# 514_outin_arduino.net
KiCad netlist of a schematic drawn in EAGLE
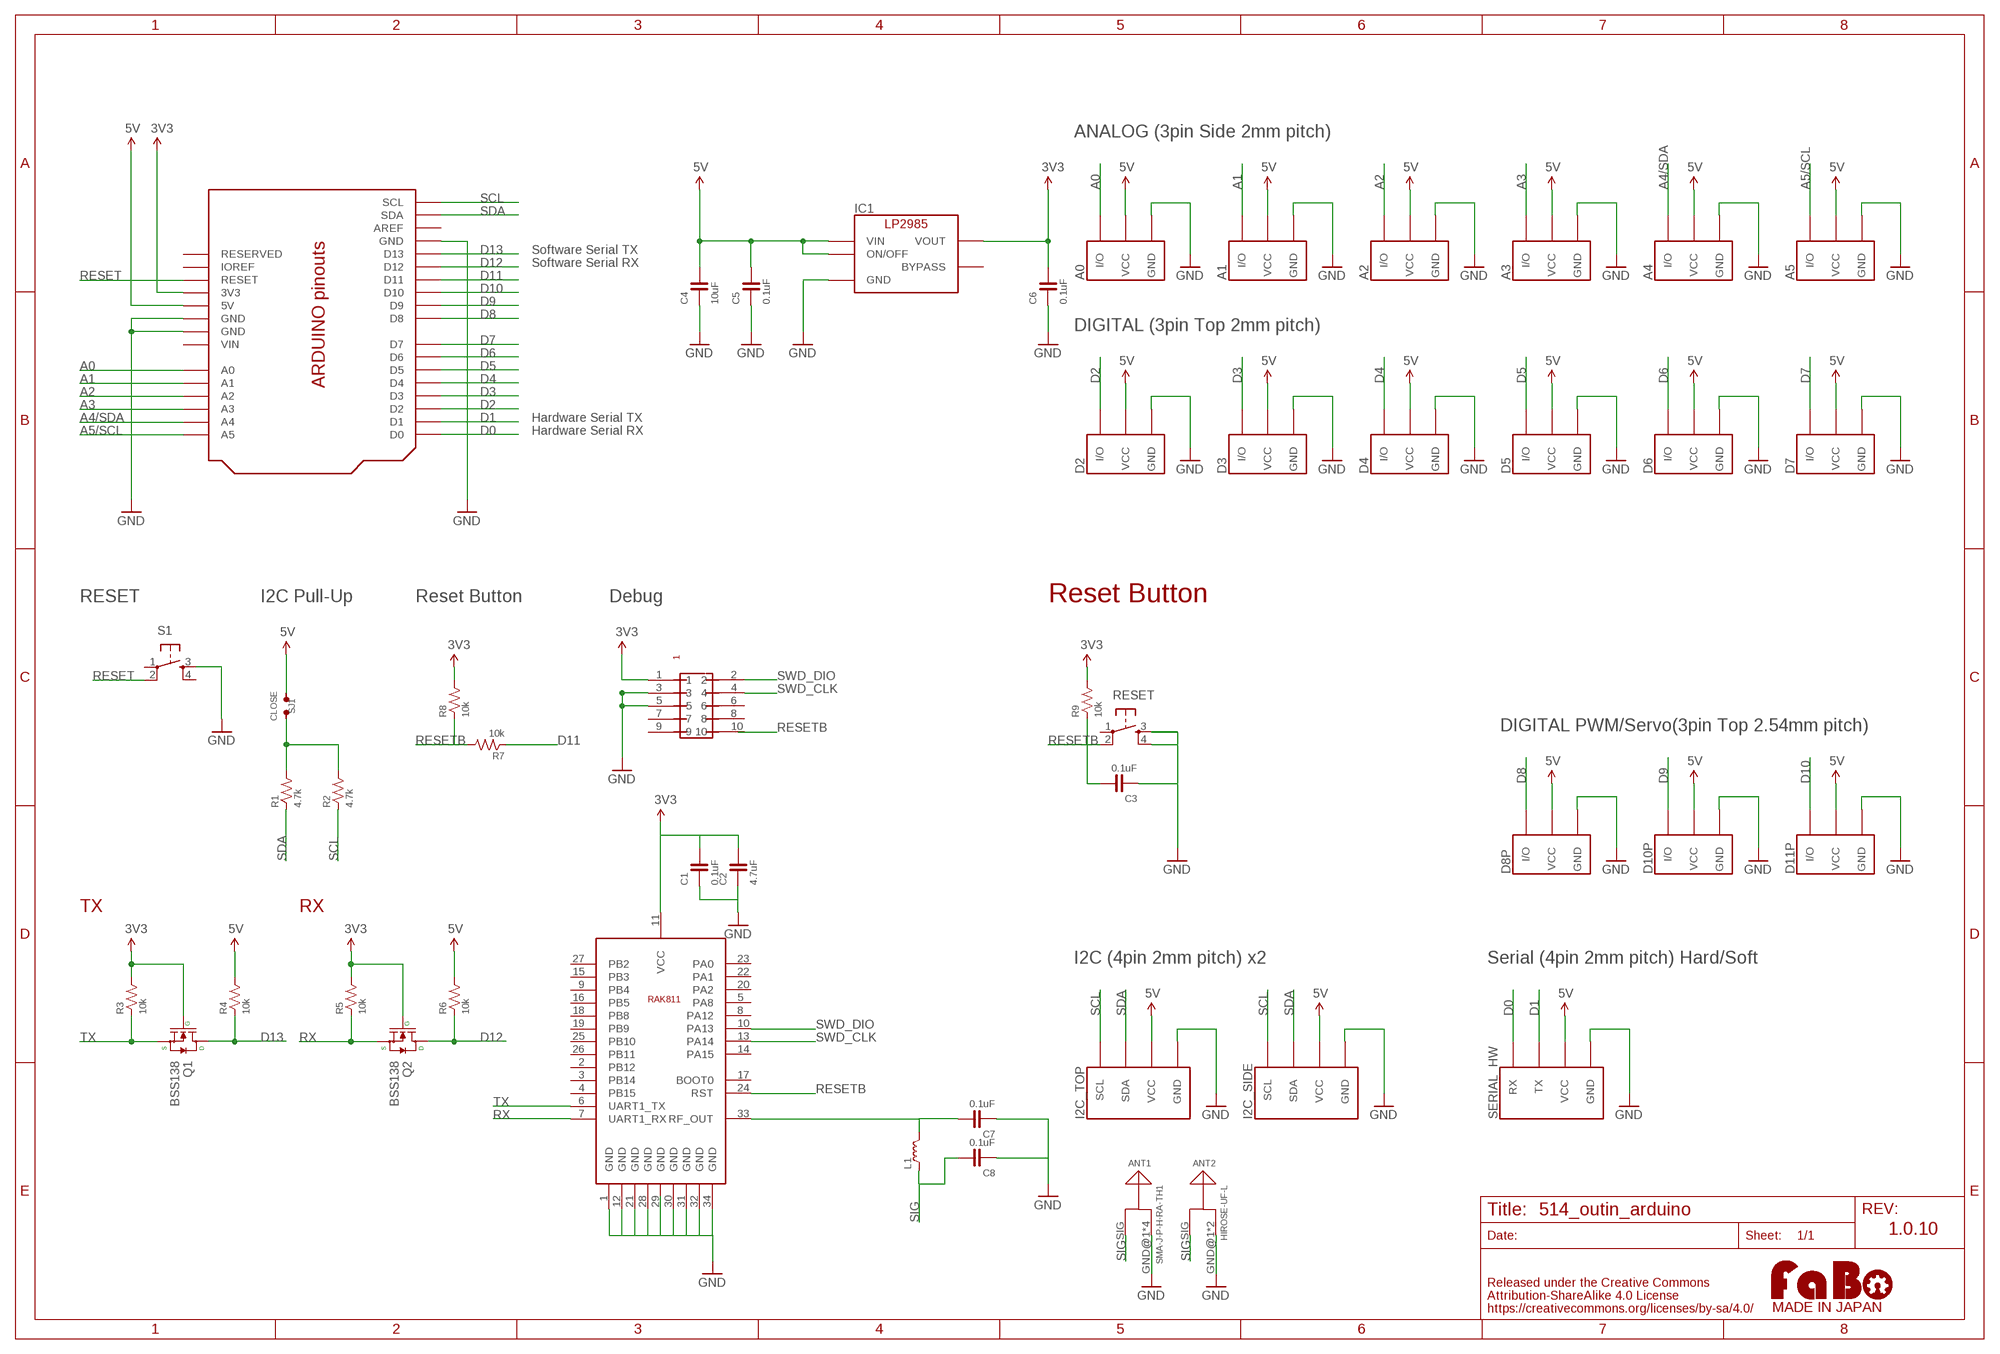
[diagram p0: schematic, sheet 1]

(export (version "E")
  (design (tool "Eeschema 10.0.6"))
  (components
    (comp (ref "A0")
      (value "FABO_BRICK_3PIN-S03B-PASK-2_LONG")
      (footprint "eagle-import:FABO_BRICK_3PIN_S03B-PASK-2_LONG")
      (libsource (lib "eagle-import") (part "FABO_BRICK_3PIN-S03B-PASK-2_LONG"))
    )
    (comp (ref "A1")
      (value "FABO_BRICK_3PIN-S03B-PASK-2_LONG")
      (footprint "eagle-import:FABO_BRICK_3PIN_S03B-PASK-2_LONG")
      (libsource (lib "eagle-import") (part "FABO_BRICK_3PIN-S03B-PASK-2_LONG"))
    )
    (comp (ref "A2")
      (value "FABO_BRICK_3PIN-S03B-PASK-2_LONG")
      (footprint "eagle-import:FABO_BRICK_3PIN_S03B-PASK-2_LONG")
      (libsource (lib "eagle-import") (part "FABO_BRICK_3PIN-S03B-PASK-2_LONG"))
    )
    (comp (ref "A3")
      (value "FABO_BRICK_3PIN-S03B-PASK-2_LONG")
      (footprint "eagle-import:FABO_BRICK_3PIN_S03B-PASK-2_LONG")
      (libsource (lib "eagle-import") (part "FABO_BRICK_3PIN-S03B-PASK-2_LONG"))
    )
    (comp (ref "A4")
      (value "FABO_BRICK_3PIN-S03B-PASK-2_LONG")
      (footprint "eagle-import:FABO_BRICK_3PIN_S03B-PASK-2_LONG")
      (libsource (lib "eagle-import") (part "FABO_BRICK_3PIN-S03B-PASK-2_LONG"))
    )
    (comp (ref "A5")
      (value "FABO_BRICK_3PIN-S03B-PASK-2_LONG")
      (footprint "eagle-import:FABO_BRICK_3PIN_S03B-PASK-2_LONG")
      (libsource (lib "eagle-import") (part "FABO_BRICK_3PIN-S03B-PASK-2_LONG"))
    )
    (comp (ref "ANT1")
      (value "SMA-J-P-H-RA-TH1")
      (footprint "eagle-import:SMA–J–P–H–RA–TH1")
      (libsource (lib "eagle-import") (part "ANTENA_SMA-J-P-H-RA-TH1"))
    )
    (comp (ref "ANT2")
      (value "HIROSE-UF-L")
      (footprint "eagle-import:HIROSE-UF-L")
      (libsource (lib "eagle-import") (part "ANTENA_HIROSE-UF-L"))
    )
    (comp (ref "C1")
      (value "0.1uF")
      (footprint "eagle-import:0603-NARROW")
      (libsource (lib "eagle-import") (part "CAPACITOR-0603_NARROW"))
    )
    (comp (ref "C2")
      (value "4.7uF")
      (footprint "eagle-import:0603-NARROW")
      (libsource (lib "eagle-import") (part "CAPACITOR-0603_NARROW"))
    )
    (comp (ref "C3")
      (value "0.1uF")
      (footprint "eagle-import:0603-NARROW")
      (libsource (lib "eagle-import") (part "CAPACITOR-0603_NARROW"))
    )
    (comp (ref "C4")
      (value "10uF")
      (footprint "eagle-import:0603-NARROW")
      (libsource (lib "eagle-import") (part "CAPACITOR-0603_NARROW"))
    )
    (comp (ref "C5")
      (value "0.1uF")
      (footprint "eagle-import:0603-NARROW")
      (libsource (lib "eagle-import") (part "CAPACITOR-0603_NARROW"))
    )
    (comp (ref "C6")
      (value "0.1uF")
      (footprint "eagle-import:0603-NARROW")
      (libsource (lib "eagle-import") (part "CAPACITOR-0603_NARROW"))
    )
    (comp (ref "C7")
      (value "0.1uF")
      (footprint "eagle-import:0603-NARROW")
      (libsource (lib "eagle-import") (part "CAPACITOR-0603_NARROW"))
    )
    (comp (ref "C8")
      (value "0.1uF")
      (footprint "eagle-import:0603-NARROW")
      (libsource (lib "eagle-import") (part "CAPACITOR-0603_NARROW"))
    )
    (comp (ref "D2")
      (value "FABO_BRICK_3PIN-B03B-PASK-1")
      (footprint "eagle-import:FABO_BRICK_3PIN_B03B-PASK-1")
      (libsource (lib "eagle-import") (part "FABO_BRICK_3PIN-B03B-PASK-1"))
    )
    (comp (ref "D3")
      (value "FABO_BRICK_3PIN-B03B-PASK-1")
      (footprint "eagle-import:FABO_BRICK_3PIN_B03B-PASK-1")
      (libsource (lib "eagle-import") (part "FABO_BRICK_3PIN-B03B-PASK-1"))
    )
    (comp (ref "D4")
      (value "FABO_BRICK_3PIN-B03B-PASK-1")
      (footprint "eagle-import:FABO_BRICK_3PIN_B03B-PASK-1")
      (libsource (lib "eagle-import") (part "FABO_BRICK_3PIN-B03B-PASK-1"))
    )
    (comp (ref "D5")
      (value "FABO_BRICK_3PIN-B03B-PASK-1")
      (footprint "eagle-import:FABO_BRICK_3PIN_B03B-PASK-1")
      (libsource (lib "eagle-import") (part "FABO_BRICK_3PIN-B03B-PASK-1"))
    )
    (comp (ref "D6")
      (value "FABO_BRICK_3PIN-B03B-PASK-1")
      (footprint "eagle-import:FABO_BRICK_3PIN_B03B-PASK-1")
      (libsource (lib "eagle-import") (part "FABO_BRICK_3PIN-B03B-PASK-1"))
    )
    (comp (ref "D7")
      (value "FABO_BRICK_3PIN-B03B-PASK-1")
      (footprint "eagle-import:FABO_BRICK_3PIN_B03B-PASK-1")
      (libsource (lib "eagle-import") (part "FABO_BRICK_3PIN-B03B-PASK-1"))
    )
    (comp (ref "D8P")
      (value "FABO_BRICK_3PIN-HEADER")
      (footprint "eagle-import:FABO_BRICK_3PIN_HEADER")
      (libsource (lib "eagle-import") (part "FABO_BRICK_3PIN-HEADER"))
    )
    (comp (ref "D10P")
      (value "FABO_BRICK_3PIN-HEADER")
      (footprint "eagle-import:FABO_BRICK_3PIN_HEADER")
      (libsource (lib "eagle-import") (part "FABO_BRICK_3PIN-HEADER"))
    )
    (comp (ref "D11P")
      (value "FABO_BRICK_3PIN-HEADER")
      (footprint "eagle-import:FABO_BRICK_3PIN_HEADER")
      (libsource (lib "eagle-import") (part "FABO_BRICK_3PIN-HEADER"))
    )
    (comp (ref "I2C_SIDE")
      (value "FABO_BRICK_I2C-S04B-PASK-2_LONG")
      (footprint "eagle-import:FABO_BRICK_I2C_S04B-PASK-2_LONG")
      (libsource (lib "eagle-import") (part "FABO_BRICK_I2C-S04B-PASK-2_LONG"))
    )
    (comp (ref "I2C_TOP")
      (value "FABO_BRICK_I2C-B04B-PASK-1")
      (footprint "eagle-import:FABO_BRICK_I2C_B04B-PASK-1")
      (libsource (lib "eagle-import") (part "FABO_BRICK_I2C-B04B-PASK-1"))
    )
    (comp (ref "IC1")
      (value "LP2985-33DBV")
      (footprint "eagle-import:SOT-23-5")
      (libsource (lib "eagle-import") (part "LP2985-33DBV"))
    )
    (comp (ref "L1")
      (value "COIL-0603")
      (footprint "eagle-import:0603")
      (libsource (lib "eagle-import") (part "COIL-0603"))
    )
    (comp (ref "Q1")
      (value "BSS138")
      (footprint "eagle-import:SOT23-3")
      (libsource (lib "eagle-import") (part "MOSFET-N"))
    )
    (comp (ref "Q2")
      (value "BSS138")
      (footprint "eagle-import:SOT23-3")
      (libsource (lib "eagle-import") (part "MOSFET-N"))
    )
    (comp (ref "R1")
      (value "4.7k")
      (footprint "eagle-import:0603")
      (libsource (lib "eagle-import") (part "RESISTOR-0603"))
    )
    (comp (ref "R2")
      (value "4.7k")
      (footprint "eagle-import:0603")
      (libsource (lib "eagle-import") (part "RESISTOR-0603"))
    )
    (comp (ref "R3")
      (value "10k")
      (footprint "eagle-import:0603-NARROW")
      (libsource (lib "eagle-import") (part "RESISTOR-0603-NARROW"))
    )
    (comp (ref "R4")
      (value "10k")
      (footprint "eagle-import:0603-NARROW")
      (libsource (lib "eagle-import") (part "RESISTOR-0603-NARROW"))
    )
    (comp (ref "R5")
      (value "10k")
      (footprint "eagle-import:0603-NARROW")
      (libsource (lib "eagle-import") (part "RESISTOR-0603-NARROW"))
    )
    (comp (ref "R6")
      (value "10k")
      (footprint "eagle-import:0603-NARROW")
      (libsource (lib "eagle-import") (part "RESISTOR-0603-NARROW"))
    )
    (comp (ref "R7")
      (value "10k")
      (footprint "eagle-import:0603-NARROW")
      (libsource (lib "eagle-import") (part "RESISTOR-0603-NARROW"))
    )
    (comp (ref "R8")
      (value "10k")
      (footprint "eagle-import:0603-NARROW")
      (libsource (lib "eagle-import") (part "RESISTOR-0603-NARROW"))
    )
    (comp (ref "R9")
      (value "10k")
      (footprint "eagle-import:0603-NARROW")
      (libsource (lib "eagle-import") (part "RESISTOR-0603-NARROW"))
    )
    (comp (ref "RESET")
      (value "TACT-SWITCH-SMD_KMR2")
      (footprint "eagle-import:KMR2")
      (libsource (lib "eagle-import") (part "TACT-SWITCH-SMD_KMR2"))
    )
    (comp (ref "S1")
      (value "TACT-SWITCH-6MM")
      (footprint "eagle-import:DTS_6_V")
      (libsource (lib "eagle-import") (part "TACT-SWITCH-6MM"))
    )
    (comp (ref "SERIAL_HW")
      (value "FABO_BRICK_SERIAL-B04B-PASK-1")
      (footprint "eagle-import:FABO_BRICK_SERIAL_B04B-PASK-1")
      (libsource (lib "eagle-import") (part "FABO_BRICK_SERIAL-B04B-PASK-1"))
    )
    (comp (ref "SJ1")
      (value "CLOSE")
      (footprint "eagle-import:SMD-JUMPER-0603")
      (libsource (lib "eagle-import") (part "SMD-JUMPER-2-0603"))
    )
    (comp (ref "U$3")
      (value "RAK811")
      (footprint "eagle-import:RAK811")
      (libsource (lib "eagle-import") (part "RAK811"))
    )
    (comp (ref "U$10")
      (value "LOGO_FABO-M")
      (footprint "eagle-import:LOGO_FABO_MS")
      (libsource (lib "eagle-import") (part "LOGO_FABO-M"))
    )
    (comp (ref "U$15")
      (value "PIN-HEADER-SMT(1.27MM)2X5")
      (footprint "eagle-import:PIN-HEADER-SMT(1.27MM)2X5")
      (libsource (lib "eagle-import") (part "PIN-HEADER-SMT(1.27MM)2X5"))
    )
    (comp (ref "U1")
      (value "ARDUINO_UNO_R3_SHIELD-OUTIN")
      (footprint "eagle-import:ARDUINO_SHIELD_OUTIN")
      (libsource (lib "eagle-import") (part "ARDUINO_UNO_R3_SHIELD-OUTIN"))
    )
  )
  (nets
    (net (code "1") (name "/A0") (class "Default")
      (node (ref "A0") (pin "I/O") (pinfunction "I/O_I/O") (pintype "bidirectional"))
      (node (ref "U1") (pin "A0") (pinfunction "A0_A0") (pintype "bidirectional"))
    )
    (net (code "2") (name "/A1") (class "Default")
      (node (ref "A1") (pin "I/O") (pinfunction "I/O_I/O") (pintype "bidirectional"))
      (node (ref "U1") (pin "A1") (pinfunction "A1_A1") (pintype "bidirectional"))
    )
    (net (code "3") (name "/A2") (class "Default")
      (node (ref "A2") (pin "I/O") (pinfunction "I/O_I/O") (pintype "bidirectional"))
      (node (ref "U1") (pin "A2") (pinfunction "A2_A2") (pintype "bidirectional"))
    )
    (net (code "4") (name "/A3") (class "Default")
      (node (ref "A3") (pin "I/O") (pinfunction "I/O_I/O") (pintype "bidirectional"))
      (node (ref "U1") (pin "A3") (pinfunction "A3_A3") (pintype "bidirectional"))
    )
    (net (code "5") (name "/A4{slash}SDA") (class "Default")
      (node (ref "A4") (pin "I/O") (pinfunction "I/O_I/O") (pintype "bidirectional"))
      (node (ref "U1") (pin "A4") (pinfunction "A4_A4") (pintype "bidirectional"))
    )
    (net (code "6") (name "/A5{slash}SCL") (class "Default")
      (node (ref "A5") (pin "I/O") (pinfunction "I/O_I/O") (pintype "bidirectional"))
      (node (ref "U1") (pin "A5") (pinfunction "A5_A5") (pintype "bidirectional"))
    )
    (net (code "7") (name "/D0") (class "Default")
      (node (ref "SERIAL_HW") (pin "RX") (pinfunction "RX_RX") (pintype "bidirectional"))
      (node (ref "U1") (pin "D0") (pinfunction "D0_D0") (pintype "bidirectional"))
    )
    (net (code "8") (name "/D1") (class "Default")
      (node (ref "SERIAL_HW") (pin "TX") (pinfunction "TX_TX") (pintype "bidirectional"))
      (node (ref "U1") (pin "D1") (pinfunction "D1_D1") (pintype "bidirectional"))
    )
    (net (code "9") (name "/D2") (class "Default")
      (node (ref "D2") (pin "I/O") (pinfunction "I/O_I/O") (pintype "bidirectional"))
      (node (ref "U1") (pin "D2") (pinfunction "D2_D2") (pintype "bidirectional"))
    )
    (net (code "10") (name "/D3") (class "Default")
      (node (ref "D3") (pin "I/O") (pinfunction "I/O_I/O") (pintype "bidirectional"))
      (node (ref "U1") (pin "D3") (pinfunction "D3_D3") (pintype "bidirectional"))
    )
    (net (code "11") (name "/D4") (class "Default")
      (node (ref "D4") (pin "I/O") (pinfunction "I/O_I/O") (pintype "bidirectional"))
      (node (ref "U1") (pin "D4") (pinfunction "D4_D4") (pintype "bidirectional"))
    )
    (net (code "12") (name "/D5") (class "Default")
      (node (ref "D5") (pin "I/O") (pinfunction "I/O_I/O") (pintype "bidirectional"))
      (node (ref "U1") (pin "D5") (pinfunction "D5_D5") (pintype "bidirectional"))
    )
    (net (code "13") (name "/D6") (class "Default")
      (node (ref "D6") (pin "I/O") (pinfunction "I/O_I/O") (pintype "bidirectional"))
      (node (ref "U1") (pin "D6") (pinfunction "D6_D6") (pintype "bidirectional"))
    )
    (net (code "14") (name "/D7") (class "Default")
      (node (ref "D7") (pin "I/O") (pinfunction "I/O_I/O") (pintype "bidirectional"))
      (node (ref "U1") (pin "D7") (pinfunction "D7_D7") (pintype "bidirectional"))
    )
    (net (code "15") (name "/D8") (class "Default")
      (node (ref "D8P") (pin "I/O") (pinfunction "I/O_I/O") (pintype "bidirectional"))
      (node (ref "U1") (pin "D8") (pinfunction "D8_D8") (pintype "bidirectional"))
    )
    (net (code "16") (name "/D9") (class "Default")
      (node (ref "D10P") (pin "I/O") (pinfunction "I/O_I/O") (pintype "bidirectional"))
      (node (ref "U1") (pin "D9") (pinfunction "D9_D9") (pintype "bidirectional"))
    )
    (net (code "17") (name "/D10") (class "Default")
      (node (ref "D11P") (pin "I/O") (pinfunction "I/O_I/O") (pintype "bidirectional"))
      (node (ref "U1") (pin "D10") (pinfunction "D10_D10") (pintype "bidirectional"))
    )
    (net (code "18") (name "/D11") (class "Default")
      (node (ref "R7") (pin "1") (pinfunction "1_1") (pintype "bidirectional"))
      (node (ref "U1") (pin "D11") (pinfunction "D11_D11") (pintype "bidirectional"))
    )
    (net (code "19") (name "/D12") (class "Default")
      (node (ref "Q2") (pin "3") (pinfunction "D_3") (pintype "passive"))
      (node (ref "R6") (pin "1") (pinfunction "1_1") (pintype "bidirectional"))
      (node (ref "U1") (pin "D12") (pinfunction "D12_D12") (pintype "bidirectional"))
    )
    (net (code "20") (name "/D13") (class "Default")
      (node (ref "Q1") (pin "3") (pinfunction "D_3") (pintype "passive"))
      (node (ref "R4") (pin "1") (pinfunction "1_1") (pintype "bidirectional"))
      (node (ref "U1") (pin "D13") (pinfunction "D13_D13") (pintype "bidirectional"))
    )
    (net (code "21") (name "/RESET") (class "Default")
      (node (ref "S1") (pin "2") (pinfunction "2_2") (pintype "passive"))
      (node (ref "U1") (pin "RESET") (pinfunction "RESET_RESET") (pintype "bidirectional"))
    )
    (net (code "22") (name "/RESETB") (class "Default")
      (node (ref "C3") (pin "2") (pinfunction "2_2") (pintype "passive"))
      (node (ref "R7") (pin "2") (pinfunction "2_2") (pintype "bidirectional"))
      (node (ref "R8") (pin "1") (pinfunction "1_1") (pintype "bidirectional"))
      (node (ref "R9") (pin "1") (pinfunction "1_1") (pintype "bidirectional"))
      (node (ref "RESET") (pin "2") (pinfunction "2_2") (pintype "passive"))
      (node (ref "U$15") (pin "10") (pinfunction "10_10") (pintype "bidirectional"))
      (node (ref "U$3") (pin "24") (pinfunction "RST_24") (pintype "bidirectional"))
    )
    (net (code "23") (name "/RX") (class "Default")
      (node (ref "Q2") (pin "2") (pinfunction "S_2") (pintype "passive"))
      (node (ref "R5") (pin "1") (pinfunction "1_1") (pintype "bidirectional"))
      (node (ref "U$3") (pin "7") (pinfunction "UART1_RX_7") (pintype "bidirectional"))
    )
    (net (code "24") (name "/SCL") (class "Default")
      (node (ref "I2C_SIDE") (pin "SCL") (pinfunction "SCL_SCL") (pintype "bidirectional"))
      (node (ref "I2C_TOP") (pin "SCL") (pinfunction "SCL_SCL") (pintype "bidirectional"))
      (node (ref "R2") (pin "1") (pinfunction "1_1") (pintype "bidirectional"))
      (node (ref "U1") (pin "SCL") (pinfunction "SCL_SCL") (pintype "bidirectional"))
    )
    (net (code "25") (name "/SDA") (class "Default")
      (node (ref "I2C_SIDE") (pin "SDA") (pinfunction "SDA_SDA") (pintype "bidirectional"))
      (node (ref "I2C_TOP") (pin "SDA") (pinfunction "SDA_SDA") (pintype "bidirectional"))
      (node (ref "R1") (pin "1") (pinfunction "1_1") (pintype "bidirectional"))
      (node (ref "U1") (pin "SDA") (pinfunction "SDA_SDA") (pintype "bidirectional"))
    )
    (net (code "26") (name "/SIG") (class "Default")
      (node (ref "ANT1") (pin "SIG") (pinfunction "SIG_SIG") (pintype "passive"))
      (node (ref "ANT2") (pin "SIG") (pinfunction "SIG_SIG") (pintype "passive"))
      (node (ref "C8") (pin "2") (pinfunction "2_2") (pintype "passive"))
      (node (ref "L1") (pin "1") (pinfunction "1_1") (pintype "bidirectional"))
    )
    (net (code "27") (name "/SWD_CLK") (class "Default")
      (node (ref "U$15") (pin "4") (pinfunction "4_4") (pintype "bidirectional"))
      (node (ref "U$3") (pin "13") (pinfunction "PA14_13") (pintype "bidirectional"))
    )
    (net (code "28") (name "/SWD_DIO") (class "Default")
      (node (ref "U$15") (pin "2") (pinfunction "2_2") (pintype "bidirectional"))
      (node (ref "U$3") (pin "10") (pinfunction "PA13_10") (pintype "bidirectional"))
    )
    (net (code "29") (name "/TX") (class "Default")
      (node (ref "Q1") (pin "2") (pinfunction "S_2") (pintype "passive"))
      (node (ref "R3") (pin "1") (pinfunction "1_1") (pintype "bidirectional"))
      (node (ref "U$3") (pin "6") (pinfunction "UART1_TX_6") (pintype "bidirectional"))
    )
    (net (code "30") (name "/VIN") (class "Default")
      (node (ref "U1") (pin "VIN") (pinfunction "VIN_VIN") (pintype "power_in"))
    )
    (net (code "31") (name "3V3") (class "Default")
      (node (ref "C1") (pin "2") (pinfunction "2_2") (pintype "passive"))
      (node (ref "C2") (pin "2") (pinfunction "2_2") (pintype "passive"))
      (node (ref "C6") (pin "2") (pinfunction "2_2") (pintype "passive"))
      (node (ref "IC1") (pin "5") (pinfunction "VOUT_5") (pintype "output"))
      (node (ref "Q1") (pin "1") (pinfunction "G_1") (pintype "passive"))
      (node (ref "Q2") (pin "1") (pinfunction "G_1") (pintype "passive"))
      (node (ref "R3") (pin "2") (pinfunction "2_2") (pintype "bidirectional"))
      (node (ref "R5") (pin "2") (pinfunction "2_2") (pintype "bidirectional"))
      (node (ref "R8") (pin "2") (pinfunction "2_2") (pintype "bidirectional"))
      (node (ref "R9") (pin "2") (pinfunction "2_2") (pintype "bidirectional"))
      (node (ref "U$15") (pin "1") (pinfunction "1_1") (pintype "bidirectional"))
      (node (ref "U$3") (pin "11") (pinfunction "VCC_11") (pintype "bidirectional"))
      (node (ref "U1") (pin "3V3") (pinfunction "3V3_3V3") (pintype "power_in"))
    )
    (net (code "32") (name "5V") (class "Default")
      (node (ref "A0") (pin "VCC") (pinfunction "VCC_VCC") (pintype "bidirectional"))
      (node (ref "A1") (pin "VCC") (pinfunction "VCC_VCC") (pintype "bidirectional"))
      (node (ref "A2") (pin "VCC") (pinfunction "VCC_VCC") (pintype "bidirectional"))
      (node (ref "A3") (pin "VCC") (pinfunction "VCC_VCC") (pintype "bidirectional"))
      (node (ref "A4") (pin "VCC") (pinfunction "VCC_VCC") (pintype "bidirectional"))
      (node (ref "A5") (pin "VCC") (pinfunction "VCC_VCC") (pintype "bidirectional"))
      (node (ref "C4") (pin "2") (pinfunction "2_2") (pintype "passive"))
      (node (ref "C5") (pin "2") (pinfunction "2_2") (pintype "passive"))
      (node (ref "D10P") (pin "VCC") (pinfunction "VCC_VCC") (pintype "bidirectional"))
      (node (ref "D11P") (pin "VCC") (pinfunction "VCC_VCC") (pintype "bidirectional"))
      (node (ref "D2") (pin "VCC") (pinfunction "VCC_VCC") (pintype "bidirectional"))
      (node (ref "D3") (pin "VCC") (pinfunction "VCC_VCC") (pintype "bidirectional"))
      (node (ref "D4") (pin "VCC") (pinfunction "VCC_VCC") (pintype "bidirectional"))
      (node (ref "D5") (pin "VCC") (pinfunction "VCC_VCC") (pintype "bidirectional"))
      (node (ref "D6") (pin "VCC") (pinfunction "VCC_VCC") (pintype "bidirectional"))
      (node (ref "D7") (pin "VCC") (pinfunction "VCC_VCC") (pintype "bidirectional"))
      (node (ref "D8P") (pin "VCC") (pinfunction "VCC_VCC") (pintype "bidirectional"))
      (node (ref "I2C_SIDE") (pin "VCC") (pinfunction "VCC_VCC") (pintype "bidirectional"))
      (node (ref "I2C_TOP") (pin "VCC") (pinfunction "VCC_VCC") (pintype "bidirectional"))
      (node (ref "IC1") (pin "1") (pinfunction "VIN_1") (pintype "input"))
      (node (ref "IC1") (pin "3") (pinfunction "ON/OFF_3") (pintype "input"))
      (node (ref "R4") (pin "2") (pinfunction "2_2") (pintype "bidirectional"))
      (node (ref "R6") (pin "2") (pinfunction "2_2") (pintype "bidirectional"))
      (node (ref "SERIAL_HW") (pin "VCC") (pinfunction "VCC_VCC") (pintype "bidirectional"))
      (node (ref "SJ1") (pin "1") (pinfunction "1_1") (pintype "passive"))
      (node (ref "U1") (pin "5V") (pinfunction "5V_5V") (pintype "power_in"))
    )
    (net (code "33") (name "GND") (class "Default")
      (node (ref "A0") (pin "GND") (pinfunction "GND_GND") (pintype "bidirectional"))
      (node (ref "A1") (pin "GND") (pinfunction "GND_GND") (pintype "bidirectional"))
      (node (ref "A2") (pin "GND") (pinfunction "GND_GND") (pintype "bidirectional"))
      (node (ref "A3") (pin "GND") (pinfunction "GND_GND") (pintype "bidirectional"))
      (node (ref "A4") (pin "GND") (pinfunction "GND_GND") (pintype "bidirectional"))
      (node (ref "A5") (pin "GND") (pinfunction "GND_GND") (pintype "bidirectional"))
      (node (ref "ANT1") (pin "GND@1") (pinfunction "GND_GND@1") (pintype "passive"))
      (node (ref "ANT1") (pin "GND@2") (pinfunction "GND_GND@2") (pintype "passive"))
      (node (ref "ANT1") (pin "GND@3") (pinfunction "GND_GND@3") (pintype "passive"))
      (node (ref "ANT1") (pin "GND@4") (pinfunction "GND_GND@4") (pintype "passive"))
      (node (ref "ANT2") (pin "GND@1") (pinfunction "GND_GND@1") (pintype "passive"))
      (node (ref "ANT2") (pin "GND@2") (pinfunction "GND_GND@2") (pintype "passive"))
      (node (ref "C1") (pin "1") (pinfunction "1_1") (pintype "passive"))
      (node (ref "C2") (pin "1") (pinfunction "1_1") (pintype "passive"))
      (node (ref "C3") (pin "1") (pinfunction "1_1") (pintype "passive"))
      (node (ref "C4") (pin "1") (pinfunction "1_1") (pintype "passive"))
      (node (ref "C5") (pin "1") (pinfunction "1_1") (pintype "passive"))
      (node (ref "C6") (pin "1") (pinfunction "1_1") (pintype "passive"))
      (node (ref "C7") (pin "1") (pinfunction "1_1") (pintype "passive"))
      (node (ref "C8") (pin "1") (pinfunction "1_1") (pintype "passive"))
      (node (ref "D10P") (pin "GND") (pinfunction "GND_GND") (pintype "bidirectional"))
      (node (ref "D11P") (pin "GND") (pinfunction "GND_GND") (pintype "bidirectional"))
      (node (ref "D2") (pin "GND") (pinfunction "GND_GND") (pintype "bidirectional"))
      (node (ref "D3") (pin "GND") (pinfunction "GND_GND") (pintype "bidirectional"))
      (node (ref "D4") (pin "GND") (pinfunction "GND_GND") (pintype "bidirectional"))
      (node (ref "D5") (pin "GND") (pinfunction "GND_GND") (pintype "bidirectional"))
      (node (ref "D6") (pin "GND") (pinfunction "GND_GND") (pintype "bidirectional"))
      (node (ref "D7") (pin "GND") (pinfunction "GND_GND") (pintype "bidirectional"))
      (node (ref "D8P") (pin "GND") (pinfunction "GND_GND") (pintype "bidirectional"))
      (node (ref "I2C_SIDE") (pin "GND") (pinfunction "GND_GND") (pintype "bidirectional"))
      (node (ref "I2C_TOP") (pin "GND") (pinfunction "GND_GND") (pintype "bidirectional"))
      (node (ref "IC1") (pin "2") (pinfunction "GND_2") (pintype "power_in"))
      (node (ref "RESET") (pin "3") (pinfunction "3_3") (pintype "passive"))
      (node (ref "RESET") (pin "4") (pinfunction "4_4") (pintype "passive"))
      (node (ref "S1") (pin "3") (pinfunction "3_3") (pintype "passive"))
      (node (ref "SERIAL_HW") (pin "GND") (pinfunction "GND_GND") (pintype "bidirectional"))
      (node (ref "U$15") (pin "3") (pinfunction "3_3") (pintype "bidirectional"))
      (node (ref "U$15") (pin "5") (pinfunction "5_5") (pintype "bidirectional"))
      (node (ref "U$3") (pin "1") (pinfunction "GND_1") (pintype "bidirectional"))
      (node (ref "U$3") (pin "12") (pinfunction "GND_12") (pintype "bidirectional"))
      (node (ref "U$3") (pin "21") (pinfunction "GND_21") (pintype "bidirectional"))
      (node (ref "U$3") (pin "28") (pinfunction "GND_28") (pintype "bidirectional"))
      (node (ref "U$3") (pin "30") (pinfunction "GND_30") (pintype "bidirectional"))
      (node (ref "U$3") (pin "31") (pinfunction "GND_31") (pintype "bidirectional"))
      (node (ref "U$3") (pin "32") (pinfunction "GND_32") (pintype "bidirectional"))
      (node (ref "U$3") (pin "34") (pinfunction "GND_34") (pintype "bidirectional"))
      (node (ref "U1") (pin "GND1") (pinfunction "GND_GND1") (pintype "power_in"))
      (node (ref "U1") (pin "GND2") (pinfunction "GND_GND2") (pintype "power_in"))
      (node (ref "U1") (pin "GND3") (pinfunction "GND_GND3") (pintype "power_in"))
    )
    (net (code "34") (name "Net-(R1-Pad2)") (class "Default")
      (node (ref "R1") (pin "2") (pinfunction "2_2") (pintype "bidirectional"))
      (node (ref "R2") (pin "2") (pinfunction "2_2") (pintype "bidirectional"))
      (node (ref "SJ1") (pin "2") (pinfunction "2_2") (pintype "passive"))
    )
    (net (code "35") (name "Net-(U$3-RF_OUT)") (class "Default")
      (node (ref "C7") (pin "2") (pinfunction "2_2") (pintype "passive"))
      (node (ref "L1") (pin "2") (pinfunction "2_2") (pintype "bidirectional"))
      (node (ref "U$3") (pin "33") (pinfunction "RF_OUT_33") (pintype "bidirectional"))
    )
    (net (code "36") (name "unconnected-(IC1-BYPASS-Pad4)") (class "Default")
      (node (ref "IC1") (pin "4") (pinfunction "BYPASS_4") (pintype "bidirectional"))
    )
    (net (code "37") (name "unconnected-(RESET-Pad1)") (class "Default")
      (node (ref "RESET") (pin "1") (pinfunction "1_1") (pintype "passive"))
    )
    (net (code "38") (name "unconnected-(S1-Pad1)") (class "Default")
      (node (ref "S1") (pin "1") (pinfunction "1_1") (pintype "passive"))
    )
    (net (code "39") (name "unconnected-(S1-Pad4)") (class "Default")
      (node (ref "S1") (pin "4") (pinfunction "4_4") (pintype "passive"))
    )
    (net (code "40") (name "unconnected-(U$3-BOOT0-Pad17)") (class "Default")
      (node (ref "U$3") (pin "17") (pinfunction "BOOT0_17") (pintype "bidirectional"))
    )
    (net (code "41") (name "unconnected-(U$3-GND-Pad29)") (class "Default")
      (node (ref "U$3") (pin "29") (pinfunction "GND_29") (pintype "bidirectional"))
    )
    (net (code "42") (name "unconnected-(U$3-PA0-Pad23)") (class "Default")
      (node (ref "U$3") (pin "23") (pinfunction "PA0_23") (pintype "bidirectional"))
    )
    (net (code "43") (name "unconnected-(U$3-PA1-Pad22)") (class "Default")
      (node (ref "U$3") (pin "22") (pinfunction "PA1_22") (pintype "bidirectional"))
    )
    (net (code "44") (name "unconnected-(U$3-PA2-Pad20)") (class "Default")
      (node (ref "U$3") (pin "20") (pinfunction "PA2_20") (pintype "bidirectional"))
    )
    (net (code "45") (name "unconnected-(U$3-PA8-Pad5)") (class "Default")
      (node (ref "U$3") (pin "5") (pinfunction "PA8_5") (pintype "bidirectional"))
    )
    (net (code "46") (name "unconnected-(U$3-PA12-Pad8)") (class "Default")
      (node (ref "U$3") (pin "8") (pinfunction "PA12_8") (pintype "bidirectional"))
    )
    (net (code "47") (name "unconnected-(U$3-PA15-Pad14)") (class "Default")
      (node (ref "U$3") (pin "14") (pinfunction "PA15_14") (pintype "bidirectional"))
    )
    (net (code "48") (name "unconnected-(U$3-PB2-Pad27)") (class "Default")
      (node (ref "U$3") (pin "27") (pinfunction "PB2_27") (pintype "bidirectional"))
    )
    (net (code "49") (name "unconnected-(U$3-PB3-Pad15)") (class "Default")
      (node (ref "U$3") (pin "15") (pinfunction "PB3_15") (pintype "bidirectional"))
    )
    (net (code "50") (name "unconnected-(U$3-PB4-Pad9)") (class "Default")
      (node (ref "U$3") (pin "9") (pinfunction "PB4_9") (pintype "bidirectional"))
    )
    (net (code "51") (name "unconnected-(U$3-PB5-Pad16)") (class "Default")
      (node (ref "U$3") (pin "16") (pinfunction "PB5_16") (pintype "bidirectional"))
    )
    (net (code "52") (name "unconnected-(U$3-PB8-Pad18)") (class "Default")
      (node (ref "U$3") (pin "18") (pinfunction "PB8_18") (pintype "bidirectional"))
    )
    (net (code "53") (name "unconnected-(U$3-PB9-Pad19)") (class "Default")
      (node (ref "U$3") (pin "19") (pinfunction "PB9_19") (pintype "bidirectional"))
    )
    (net (code "54") (name "unconnected-(U$3-PB10-Pad25)") (class "Default")
      (node (ref "U$3") (pin "25") (pinfunction "PB10_25") (pintype "bidirectional"))
    )
    (net (code "55") (name "unconnected-(U$3-PB11-Pad26)") (class "Default")
      (node (ref "U$3") (pin "26") (pinfunction "PB11_26") (pintype "bidirectional"))
    )
    (net (code "56") (name "unconnected-(U$3-PB12-Pad2)") (class "Default")
      (node (ref "U$3") (pin "2") (pinfunction "PB12_2") (pintype "bidirectional"))
    )
    (net (code "57") (name "unconnected-(U$3-PB14-Pad3)") (class "Default")
      (node (ref "U$3") (pin "3") (pinfunction "PB14_3") (pintype "bidirectional"))
    )
    (net (code "58") (name "unconnected-(U$3-PB15-Pad4)") (class "Default")
      (node (ref "U$3") (pin "4") (pinfunction "PB15_4") (pintype "bidirectional"))
    )
    (net (code "59") (name "unconnected-(U$15-Pad6)") (class "Default")
      (node (ref "U$15") (pin "6") (pinfunction "6_6") (pintype "bidirectional"))
    )
    (net (code "60") (name "unconnected-(U$15-Pad7)") (class "Default")
      (node (ref "U$15") (pin "7") (pinfunction "7_7") (pintype "bidirectional"))
    )
    (net (code "61") (name "unconnected-(U$15-Pad8)") (class "Default")
      (node (ref "U$15") (pin "8") (pinfunction "8_8") (pintype "bidirectional"))
    )
    (net (code "62") (name "unconnected-(U$15-Pad9)") (class "Default")
      (node (ref "U$15") (pin "9") (pinfunction "9_9") (pintype "bidirectional"))
    )
    (net (code "63") (name "unconnected-(U1-PadAREF)") (class "Default")
      (node (ref "U1") (pin "AREF") (pinfunction "AREF_AREF") (pintype "bidirectional"))
    )
    (net (code "64") (name "unconnected-(U1-PadIOREF)") (class "Default")
      (node (ref "U1") (pin "IOREF") (pinfunction "IOREF_IOREF") (pintype "output"))
    )
    (net (code "65") (name "unconnected-(U1-PadRESERVED)") (class "Default")
      (node (ref "U1") (pin "RESERVED") (pinfunction "RESERVED_RESERVED") (pintype "no_connect"))
    )
  )
)
